# 05_CONNECTORS.net
KiCad netlist of a schematic drawn in Altium Designer
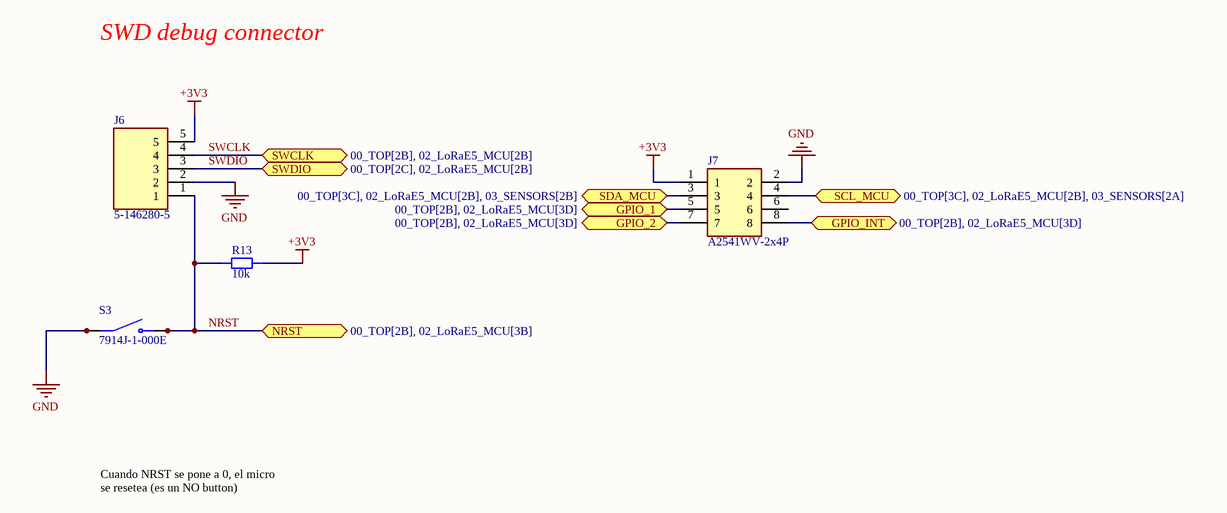
[diagram p0: 05_CONNECTORS.SchDoc]

(export (version "E")
  (design (tool "Eeschema 10.0.6"))
  (components
    (comp (ref "J6")
      (value "5-146280-5")
      (footprint "HDRV5W67P0X254_1X5_1229X234X821P")
      (description "TE CONNECTIVITY - 5-146280-5 - CONNECTOR, BOARD-TO-BOARD 07AH5929")
      (fields (field (name "MOUSER PART NUMBER") "571-5-146280-5"))
      (libsource (lib "TrashTrack_SCH_LIB") (part "5-146280-5"))
    )
    (comp (ref "J7")
      (value "A2541WV-2x4P")
      (footprint "TSW-104-XX-YY-D")
      (fields
        (field (name "MANUFACTURER_PART_NUMBER") "TSW-104-07-T-D")
        (field (name "MOUSER PART NUMBER") "200-TSW10407TD")
      )
      (libsource (lib "TrashTrack_SCH_LIB") (part "TSW-104-07-T-D"))
    )
    (comp (ref "R13")
      (value "10k")
      (footprint "Resistor_SMD:0603_1608m")
      (libsource (lib "TrashTrack_SCH_LIB") (part "Generic Resistor"))
    )
    (comp (ref "S3")
      (value "7914J-1-000E")
      (footprint "SW_7914J-1-000E")
      (description "Switch Tactile N.O. SPST Round Button J-Hook 0.1A 16VAC 16VDC 100000Cycles 2.94N SMD T/R")
      (fields (field (name "MF") "Bourns") (field (name "MP") "7914J-1-000E."))
      (libsource (lib "TrashTrack_SCH_LIB") (part "7914J-1-000E"))
    )
  )
  (nets
    (net (code "1") (name "+3V3") (class "Default")
      (node (ref "J6") (pin "5") (pinfunction "5_5") (pintype "passive"))
      (node (ref "J7") (pin "1") (pinfunction "1_1") (pintype "passive"))
      (node (ref "R13") (pin "2") (pintype "passive"))
    )
    (net (code "2") (name "/GPIO_1") (class "Default")
      (node (ref "J7") (pin "5") (pinfunction "5_5") (pintype "passive"))
    )
    (net (code "3") (name "/GPIO_2") (class "Default")
      (node (ref "J7") (pin "7") (pinfunction "7_7") (pintype "passive"))
    )
    (net (code "4") (name "/GPIO_INT") (class "Default")
      (node (ref "J7") (pin "8") (pinfunction "8_8") (pintype "passive"))
    )
    (net (code "5") (name "/NRST") (class "Default")
      (node (ref "J6") (pin "1") (pinfunction "1_1") (pintype "passive"))
      (node (ref "R13") (pin "1") (pintype "passive"))
      (node (ref "S3") (pin "3") (pinfunction "NO_3") (pintype "passive"))
      (node (ref "S3") (pin "4") (pinfunction "NO_4") (pintype "passive"))
    )
    (net (code "6") (name "/SCL_MCU") (class "Default")
      (node (ref "J7") (pin "4") (pinfunction "4_4") (pintype "passive"))
    )
    (net (code "7") (name "/SDA_MCU") (class "Default")
      (node (ref "J7") (pin "3") (pinfunction "3_3") (pintype "passive"))
    )
    (net (code "8") (name "/SWCLK") (class "Default")
      (node (ref "J6") (pin "4") (pinfunction "4_4") (pintype "passive"))
    )
    (net (code "9") (name "/SWDIO") (class "Default")
      (node (ref "J6") (pin "3") (pinfunction "3_3") (pintype "passive"))
    )
    (net (code "10") (name "GND") (class "Default")
      (node (ref "J6") (pin "2") (pinfunction "2_2") (pintype "passive"))
      (node (ref "J7") (pin "2") (pinfunction "2_2") (pintype "passive"))
      (node (ref "S3") (pin "1") (pinfunction "COM_1") (pintype "passive"))
      (node (ref "S3") (pin "2") (pinfunction "COM_2") (pintype "passive"))
    )
    (net (code "11") (name "unconnected-(J7-Pad6)") (class "Default")
      (node (ref "J7") (pin "6") (pinfunction "6_6") (pintype "passive"))
    )
  )
)
